# JTAG.net
KiCad netlist of a schematic drawn in EAGLE
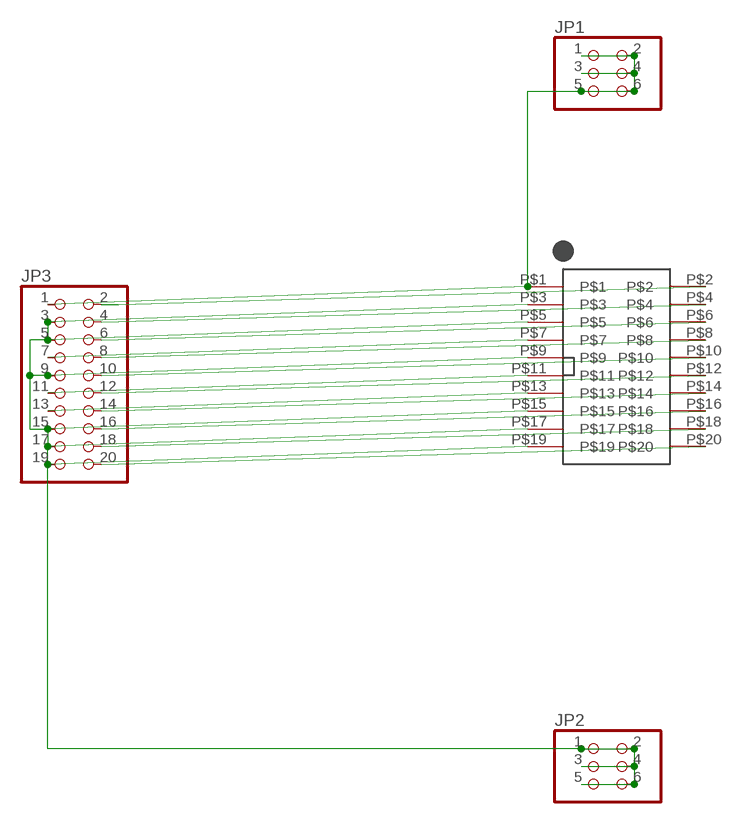
[diagram p0: schematic, sheet 1]

(export (version "E")
  (design (tool "Eeschema 10.0.6"))
  (components
    (comp (ref "JP1")
      (value "PINHD-2X3")
      (footprint "eagle-import:2X03")
      (libsource (lib "eagle-import") (part "PINHD-2X3"))
    )
    (comp (ref "JP2")
      (value "PINHD-2X3")
      (footprint "eagle-import:2X03")
      (libsource (lib "eagle-import") (part "PINHD-2X3"))
    )
    (comp (ref "JP3")
      (value "PINHD-2X10")
      (footprint "eagle-import:2X10")
      (libsource (lib "eagle-import") (part "PINHD-2X10"))
    )
    (comp (ref "U$3")
      (value "2X10JTAG")
      (footprint "eagle-import:2X10JTAG")
      (fields (field (name "MFGP") "3220-20-0100-00"))
      (libsource (lib "eagle-import") (part "2X10JTAG"))
    )
  )
  (nets
    (net (code "1") (name "Net-(JP1-Pad1)") (class "Default")
      (node (ref "JP1") (pin "1") (pinfunction "1_1") (pintype "passive"))
      (node (ref "JP1") (pin "2") (pinfunction "2_2") (pintype "passive"))
      (node (ref "JP1") (pin "3") (pinfunction "3_3") (pintype "passive"))
      (node (ref "JP1") (pin "4") (pinfunction "4_4") (pintype "passive"))
      (node (ref "JP1") (pin "5") (pinfunction "5_5") (pintype "passive"))
      (node (ref "JP1") (pin "6") (pinfunction "6_6") (pintype "passive"))
      (node (ref "JP3") (pin "1") (pinfunction "1_1") (pintype "passive"))
      (node (ref "U$3") (pin "P$1") (pinfunction "P$1_P$1") (pintype "bidirectional"))
    )
    (net (code "2") (name "Net-(JP2-Pad1)") (class "Default")
      (node (ref "JP2") (pin "1") (pinfunction "1_1") (pintype "passive"))
      (node (ref "JP2") (pin "2") (pinfunction "2_2") (pintype "passive"))
      (node (ref "JP2") (pin "3") (pinfunction "3_3") (pintype "passive"))
      (node (ref "JP2") (pin "4") (pinfunction "4_4") (pintype "passive"))
      (node (ref "JP2") (pin "5") (pinfunction "5_5") (pintype "passive"))
      (node (ref "JP2") (pin "6") (pinfunction "6_6") (pintype "passive"))
      (node (ref "JP3") (pin "15") (pinfunction "15_15") (pintype "passive"))
      (node (ref "JP3") (pin "17") (pinfunction "17_17") (pintype "passive"))
      (node (ref "JP3") (pin "19") (pinfunction "19_19") (pintype "passive"))
      (node (ref "JP3") (pin "3") (pinfunction "3_3") (pintype "passive"))
      (node (ref "JP3") (pin "5") (pinfunction "5_5") (pintype "passive"))
      (node (ref "JP3") (pin "9") (pinfunction "9_9") (pintype "passive"))
      (node (ref "U$3") (pin "P$15") (pinfunction "P$15_P$15") (pintype "bidirectional"))
      (node (ref "U$3") (pin "P$17") (pinfunction "P$17_P$17") (pintype "bidirectional"))
      (node (ref "U$3") (pin "P$19") (pinfunction "P$19_P$19") (pintype "bidirectional"))
      (node (ref "U$3") (pin "P$3") (pinfunction "P$3_P$3") (pintype "bidirectional"))
      (node (ref "U$3") (pin "P$5") (pinfunction "P$5_P$5") (pintype "bidirectional"))
      (node (ref "U$3") (pin "P$9") (pinfunction "P$9_P$9") (pintype "bidirectional"))
    )
    (net (code "3") (name "Net-(JP3-Pad2)") (class "Default")
      (node (ref "JP3") (pin "2") (pinfunction "2_2") (pintype "passive"))
      (node (ref "U$3") (pin "P$2") (pinfunction "P$2_P$2") (pintype "bidirectional"))
    )
    (net (code "4") (name "Net-(JP3-Pad4)") (class "Default")
      (node (ref "JP3") (pin "4") (pinfunction "4_4") (pintype "passive"))
      (node (ref "U$3") (pin "P$4") (pinfunction "P$4_P$4") (pintype "bidirectional"))
    )
    (net (code "5") (name "Net-(JP3-Pad6)") (class "Default")
      (node (ref "JP3") (pin "6") (pinfunction "6_6") (pintype "passive"))
      (node (ref "U$3") (pin "P$6") (pinfunction "P$6_P$6") (pintype "bidirectional"))
    )
    (net (code "6") (name "Net-(JP3-Pad7)") (class "Default")
      (node (ref "JP3") (pin "7") (pinfunction "7_7") (pintype "passive"))
      (node (ref "U$3") (pin "P$7") (pinfunction "P$7_P$7") (pintype "bidirectional"))
    )
    (net (code "7") (name "Net-(JP3-Pad8)") (class "Default")
      (node (ref "JP3") (pin "8") (pinfunction "8_8") (pintype "passive"))
      (node (ref "U$3") (pin "P$8") (pinfunction "P$8_P$8") (pintype "bidirectional"))
    )
    (net (code "8") (name "Net-(JP3-Pad10)") (class "Default")
      (node (ref "JP3") (pin "10") (pinfunction "10_10") (pintype "passive"))
      (node (ref "U$3") (pin "P$10") (pinfunction "P$10_P$10") (pintype "bidirectional"))
    )
    (net (code "9") (name "Net-(JP3-Pad11)") (class "Default")
      (node (ref "JP3") (pin "11") (pinfunction "11_11") (pintype "passive"))
      (node (ref "U$3") (pin "P$11") (pinfunction "P$11_P$11") (pintype "bidirectional"))
    )
    (net (code "10") (name "Net-(JP3-Pad12)") (class "Default")
      (node (ref "JP3") (pin "12") (pinfunction "12_12") (pintype "passive"))
      (node (ref "U$3") (pin "P$12") (pinfunction "P$12_P$12") (pintype "bidirectional"))
    )
    (net (code "11") (name "Net-(JP3-Pad13)") (class "Default")
      (node (ref "JP3") (pin "13") (pinfunction "13_13") (pintype "passive"))
      (node (ref "U$3") (pin "P$13") (pinfunction "P$13_P$13") (pintype "bidirectional"))
    )
    (net (code "12") (name "Net-(JP3-Pad14)") (class "Default")
      (node (ref "JP3") (pin "14") (pinfunction "14_14") (pintype "passive"))
      (node (ref "U$3") (pin "P$14") (pinfunction "P$14_P$14") (pintype "bidirectional"))
    )
    (net (code "13") (name "Net-(JP3-Pad16)") (class "Default")
      (node (ref "JP3") (pin "16") (pinfunction "16_16") (pintype "passive"))
      (node (ref "U$3") (pin "P$16") (pinfunction "P$16_P$16") (pintype "bidirectional"))
    )
    (net (code "14") (name "Net-(JP3-Pad18)") (class "Default")
      (node (ref "JP3") (pin "18") (pinfunction "18_18") (pintype "passive"))
      (node (ref "U$3") (pin "P$18") (pinfunction "P$18_P$18") (pintype "bidirectional"))
    )
    (net (code "15") (name "Net-(JP3-Pad20)") (class "Default")
      (node (ref "JP3") (pin "20") (pinfunction "20_20") (pintype "passive"))
      (node (ref "U$3") (pin "P$20") (pinfunction "P$20_P$20") (pintype "bidirectional"))
    )
  )
)
